# POWER.net
KiCad netlist of a schematic drawn in Altium Designer
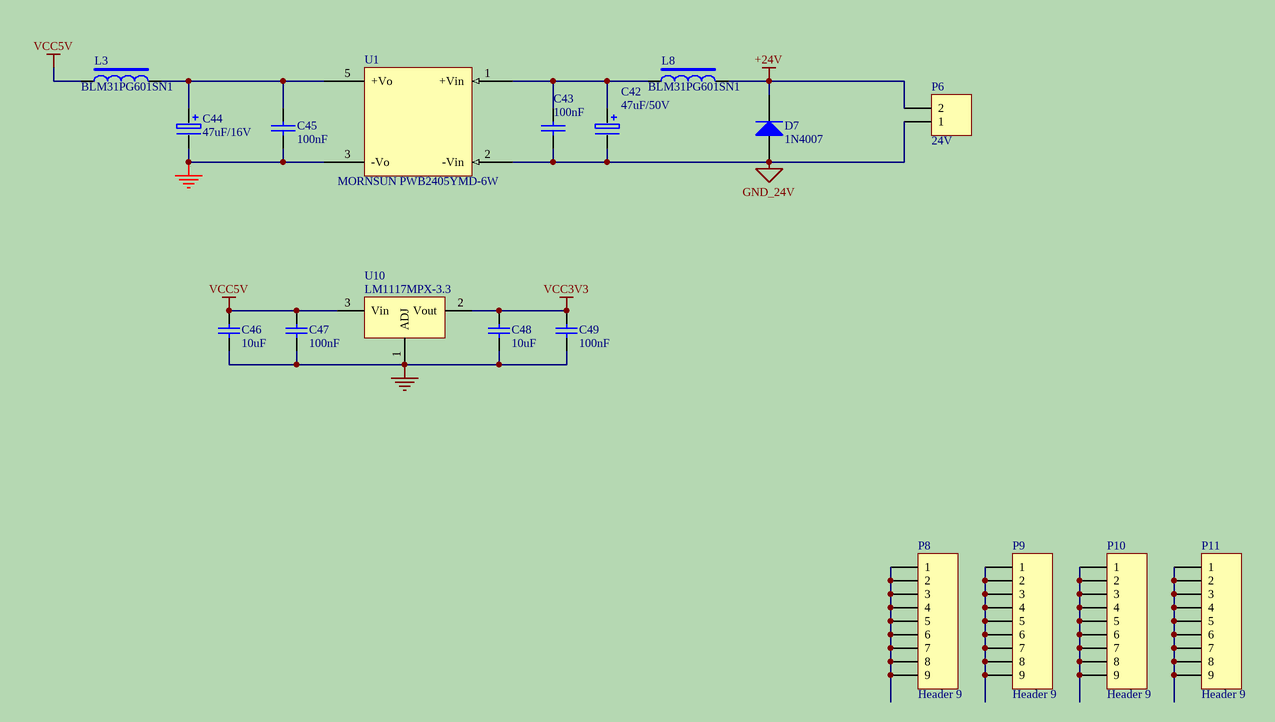
[diagram p0: POWER.SchDoc]

(export (version "E")
  (design (tool "Eeschema 10.0.6"))
  (components
    (comp (ref "C42")
      (value "47uF/50V")
      (footprint "CD1/2")
      (description "Electrolytic Capacitor")
      (libsource (lib "*") (part "CD1"))
    )
    (comp (ref "C43")
      (value "100nF")
      (footprint "C0805")
      (description "Capacitor")
      (libsource (lib "*") (part "CC"))
    )
    (comp (ref "C44")
      (value "47uF/16V")
      (footprint "CD1/2")
      (description "Electrolytic Capacitor")
      (libsource (lib "*") (part "CD1"))
    )
    (comp (ref "C45")
      (value "100nF")
      (footprint "C0805")
      (description "Capacitor")
      (libsource (lib "*") (part "CC"))
    )
    (comp (ref "C46")
      (value "10uF")
      (footprint "C1206")
      (description "Capacitor")
      (fields (field (name "PUBLISHER") "Altium Limited"))
      (libsource (lib "Miscellaneous Devices") (part "CAP"))
    )
    (comp (ref "C47")
      (value "100nF")
      (footprint "C0805")
      (description "Capacitor")
      (fields (field (name "PUBLISHER") "Altium Limited"))
      (libsource (lib "Miscellaneous Devices") (part "CAP"))
    )
    (comp (ref "C48")
      (value "10uF")
      (footprint "C1206")
      (description "Capacitor")
      (fields (field (name "PUBLISHER") "Altium Limited"))
      (libsource (lib "Miscellaneous Devices") (part "CAP"))
    )
    (comp (ref "C49")
      (value "100nF")
      (footprint "C0805")
      (description "Capacitor")
      (fields (field (name "PUBLISHER") "Altium Limited"))
      (libsource (lib "Miscellaneous Devices") (part "CAP"))
    )
    (comp (ref "D7")
      (value "1N4007")
      (footprint "DO-41")
      (description "1 Amp General Purpose Rectifier")
      (fields (field (name "PUBLISHER") "Altium Limited"))
      (libsource (lib "Miscellaneous Devices") (part "Diode 1N4007"))
    )
    (comp (ref "L3") (value "BLM31PG601SN1") (footprint "L1206") (libsource (lib "*") (part "INDUCTOR2")))
    (comp (ref "L8") (value "BLM31PG601SN1") (footprint "L1206") (libsource (lib "*") (part "INDUCTOR2")))
    (comp (ref "P6")
      (value "24V")
      (footprint "3.96-2")
      (description "Header, 2-Pin")
      (fields (field (name "PUBLISHER") "Altium Limited"))
      (libsource (lib "Miscellaneous Connectors") (part "Header 2"))
    )
    (comp (ref "P8")
      (value "Header 9")
      (footprint "lk")
      (description "Header, 9-Pin")
      (fields (field (name "PUBLISHER") "Altium Limited"))
      (libsource (lib "Miscellaneous Connectors") (part "Header 9"))
    )
    (comp (ref "P9")
      (value "Header 9")
      (footprint "lk")
      (description "Header, 9-Pin")
      (fields (field (name "PUBLISHER") "Altium Limited"))
      (libsource (lib "Miscellaneous Connectors") (part "Header 9"))
    )
    (comp (ref "P10")
      (value "Header 9")
      (footprint "lk")
      (description "Header, 9-Pin")
      (fields (field (name "PUBLISHER") "Altium Limited"))
      (libsource (lib "Miscellaneous Connectors") (part "Header 9"))
    )
    (comp (ref "P11")
      (value "Header 9")
      (footprint "lk")
      (description "Header, 9-Pin")
      (fields (field (name "PUBLISHER") "Altium Limited"))
      (libsource (lib "Miscellaneous Connectors") (part "Header 9"))
    )
    (comp (ref "U1")
      (value "MORNSUN PWB2405YMD-6W")
      (footprint "DC/DC-1X1")
      (libsource (lib "*") (part "48S5"))
    )
    (comp (ref "U10")
      (value "LM1117MPX-3.3")
      (footprint "SOT-223")
      (description "3-Terminal Adjustable Positive Voltage Regulator")
      (libsource (lib "稳压器件") (part "LM1117"))
    )
  )
  (nets
    (net (code "1") (name "+24V") (class "Default")
      (node (ref "D7") (pin "2") (pinfunction "K_2") (pintype "passive"))
      (node (ref "L8") (pin "2") (pintype "passive"))
      (node (ref "P6") (pin "2") (pinfunction "2_2") (pintype "passive"))
    )
    (net (code "2") (name "GND") (class "Default")
      (node (ref "C44") (pin "2") (pinfunction "2_2") (pintype "passive"))
      (node (ref "C45") (pin "2") (pinfunction "2_2") (pintype "passive"))
      (node (ref "C46") (pin "1") (pinfunction "1_1") (pintype "passive"))
      (node (ref "C47") (pin "1") (pinfunction "1_1") (pintype "passive"))
      (node (ref "C48") (pin "1") (pinfunction "1_1") (pintype "passive"))
      (node (ref "C49") (pin "1") (pinfunction "1_1") (pintype "passive"))
      (node (ref "U1") (pin "3") (pinfunction "-Vo_3") (pintype "power_in"))
      (node (ref "U10") (pin "1") (pinfunction "ADJ_1") (pintype "passive"))
    )
    (net (code "3") (name "GND_24V") (class "Default")
      (node (ref "C42") (pin "2") (pinfunction "2_2") (pintype "passive"))
      (node (ref "C43") (pin "2") (pinfunction "2_2") (pintype "passive"))
      (node (ref "D7") (pin "1") (pinfunction "A_1") (pintype "passive"))
      (node (ref "P6") (pin "1") (pinfunction "1_1") (pintype "passive"))
      (node (ref "U1") (pin "2") (pinfunction "-Vin_2") (pintype "input"))
    )
    (net (code "4") (name "NC") (class "Default")
      (node (ref "U1") (pin "4") (pinfunction "NC_4") (pintype "tri_state"))
    )
    (net (code "5") (name "Net-(P8-Pad1)") (class "Default")
      (node (ref "P8") (pin "1") (pinfunction "1_1") (pintype "passive"))
      (node (ref "P8") (pin "2") (pinfunction "2_2") (pintype "passive"))
      (node (ref "P8") (pin "3") (pinfunction "3_3") (pintype "passive"))
      (node (ref "P8") (pin "4") (pinfunction "4_4") (pintype "passive"))
      (node (ref "P8") (pin "5") (pinfunction "5_5") (pintype "passive"))
      (node (ref "P8") (pin "6") (pinfunction "6_6") (pintype "passive"))
      (node (ref "P8") (pin "7") (pinfunction "7_7") (pintype "passive"))
      (node (ref "P8") (pin "8") (pinfunction "8_8") (pintype "passive"))
      (node (ref "P8") (pin "9") (pinfunction "9_9") (pintype "passive"))
    )
    (net (code "6") (name "Net-(P9-Pad1)") (class "Default")
      (node (ref "P9") (pin "1") (pinfunction "1_1") (pintype "passive"))
      (node (ref "P9") (pin "2") (pinfunction "2_2") (pintype "passive"))
      (node (ref "P9") (pin "3") (pinfunction "3_3") (pintype "passive"))
      (node (ref "P9") (pin "4") (pinfunction "4_4") (pintype "passive"))
      (node (ref "P9") (pin "5") (pinfunction "5_5") (pintype "passive"))
      (node (ref "P9") (pin "6") (pinfunction "6_6") (pintype "passive"))
      (node (ref "P9") (pin "7") (pinfunction "7_7") (pintype "passive"))
      (node (ref "P9") (pin "8") (pinfunction "8_8") (pintype "passive"))
      (node (ref "P9") (pin "9") (pinfunction "9_9") (pintype "passive"))
    )
    (net (code "7") (name "Net-(P10-Pad1)") (class "Default")
      (node (ref "P10") (pin "1") (pinfunction "1_1") (pintype "passive"))
      (node (ref "P10") (pin "2") (pinfunction "2_2") (pintype "passive"))
      (node (ref "P10") (pin "3") (pinfunction "3_3") (pintype "passive"))
      (node (ref "P10") (pin "4") (pinfunction "4_4") (pintype "passive"))
      (node (ref "P10") (pin "5") (pinfunction "5_5") (pintype "passive"))
      (node (ref "P10") (pin "6") (pinfunction "6_6") (pintype "passive"))
      (node (ref "P10") (pin "7") (pinfunction "7_7") (pintype "passive"))
      (node (ref "P10") (pin "8") (pinfunction "8_8") (pintype "passive"))
      (node (ref "P10") (pin "9") (pinfunction "9_9") (pintype "passive"))
    )
    (net (code "8") (name "Net-(P11-Pad1)") (class "Default")
      (node (ref "P11") (pin "1") (pinfunction "1_1") (pintype "passive"))
      (node (ref "P11") (pin "2") (pinfunction "2_2") (pintype "passive"))
      (node (ref "P11") (pin "3") (pinfunction "3_3") (pintype "passive"))
      (node (ref "P11") (pin "4") (pinfunction "4_4") (pintype "passive"))
      (node (ref "P11") (pin "5") (pinfunction "5_5") (pintype "passive"))
      (node (ref "P11") (pin "6") (pinfunction "6_6") (pintype "passive"))
      (node (ref "P11") (pin "7") (pinfunction "7_7") (pintype "passive"))
      (node (ref "P11") (pin "8") (pinfunction "8_8") (pintype "passive"))
      (node (ref "P11") (pin "9") (pinfunction "9_9") (pintype "passive"))
    )
    (net (code "9") (name "Net-(U1-+Vin)") (class "Default")
      (node (ref "C42") (pin "1") (pinfunction "1_1") (pintype "passive"))
      (node (ref "C43") (pin "1") (pinfunction "1_1") (pintype "passive"))
      (node (ref "L8") (pin "1") (pintype "passive"))
      (node (ref "U1") (pin "1") (pinfunction "+Vin_1") (pintype "input"))
    )
    (net (code "10") (name "Net-(U1-+Vo)") (class "Default")
      (node (ref "C44") (pin "1") (pinfunction "1_1") (pintype "passive"))
      (node (ref "C45") (pin "1") (pinfunction "1_1") (pintype "passive"))
      (node (ref "L3") (pin "2") (pintype "passive"))
      (node (ref "U1") (pin "5") (pinfunction "+Vo_5") (pintype "power_in"))
    )
    (net (code "11") (name "VCC3V3") (class "Default")
      (node (ref "C48") (pin "2") (pinfunction "2_2") (pintype "passive"))
      (node (ref "C49") (pin "2") (pinfunction "2_2") (pintype "passive"))
      (node (ref "U10") (pin "2") (pinfunction "Vout_2") (pintype "passive"))
    )
    (net (code "12") (name "VCC5V") (class "Default")
      (node (ref "C46") (pin "2") (pinfunction "2_2") (pintype "passive"))
      (node (ref "C47") (pin "2") (pinfunction "2_2") (pintype "passive"))
      (node (ref "L3") (pin "1") (pintype "passive"))
      (node (ref "U10") (pin "3") (pinfunction "Vin_3") (pintype "passive"))
    )
  )
)
